# TRV_UP20.net
KiCad netlist of a schematic drawn in EAGLE
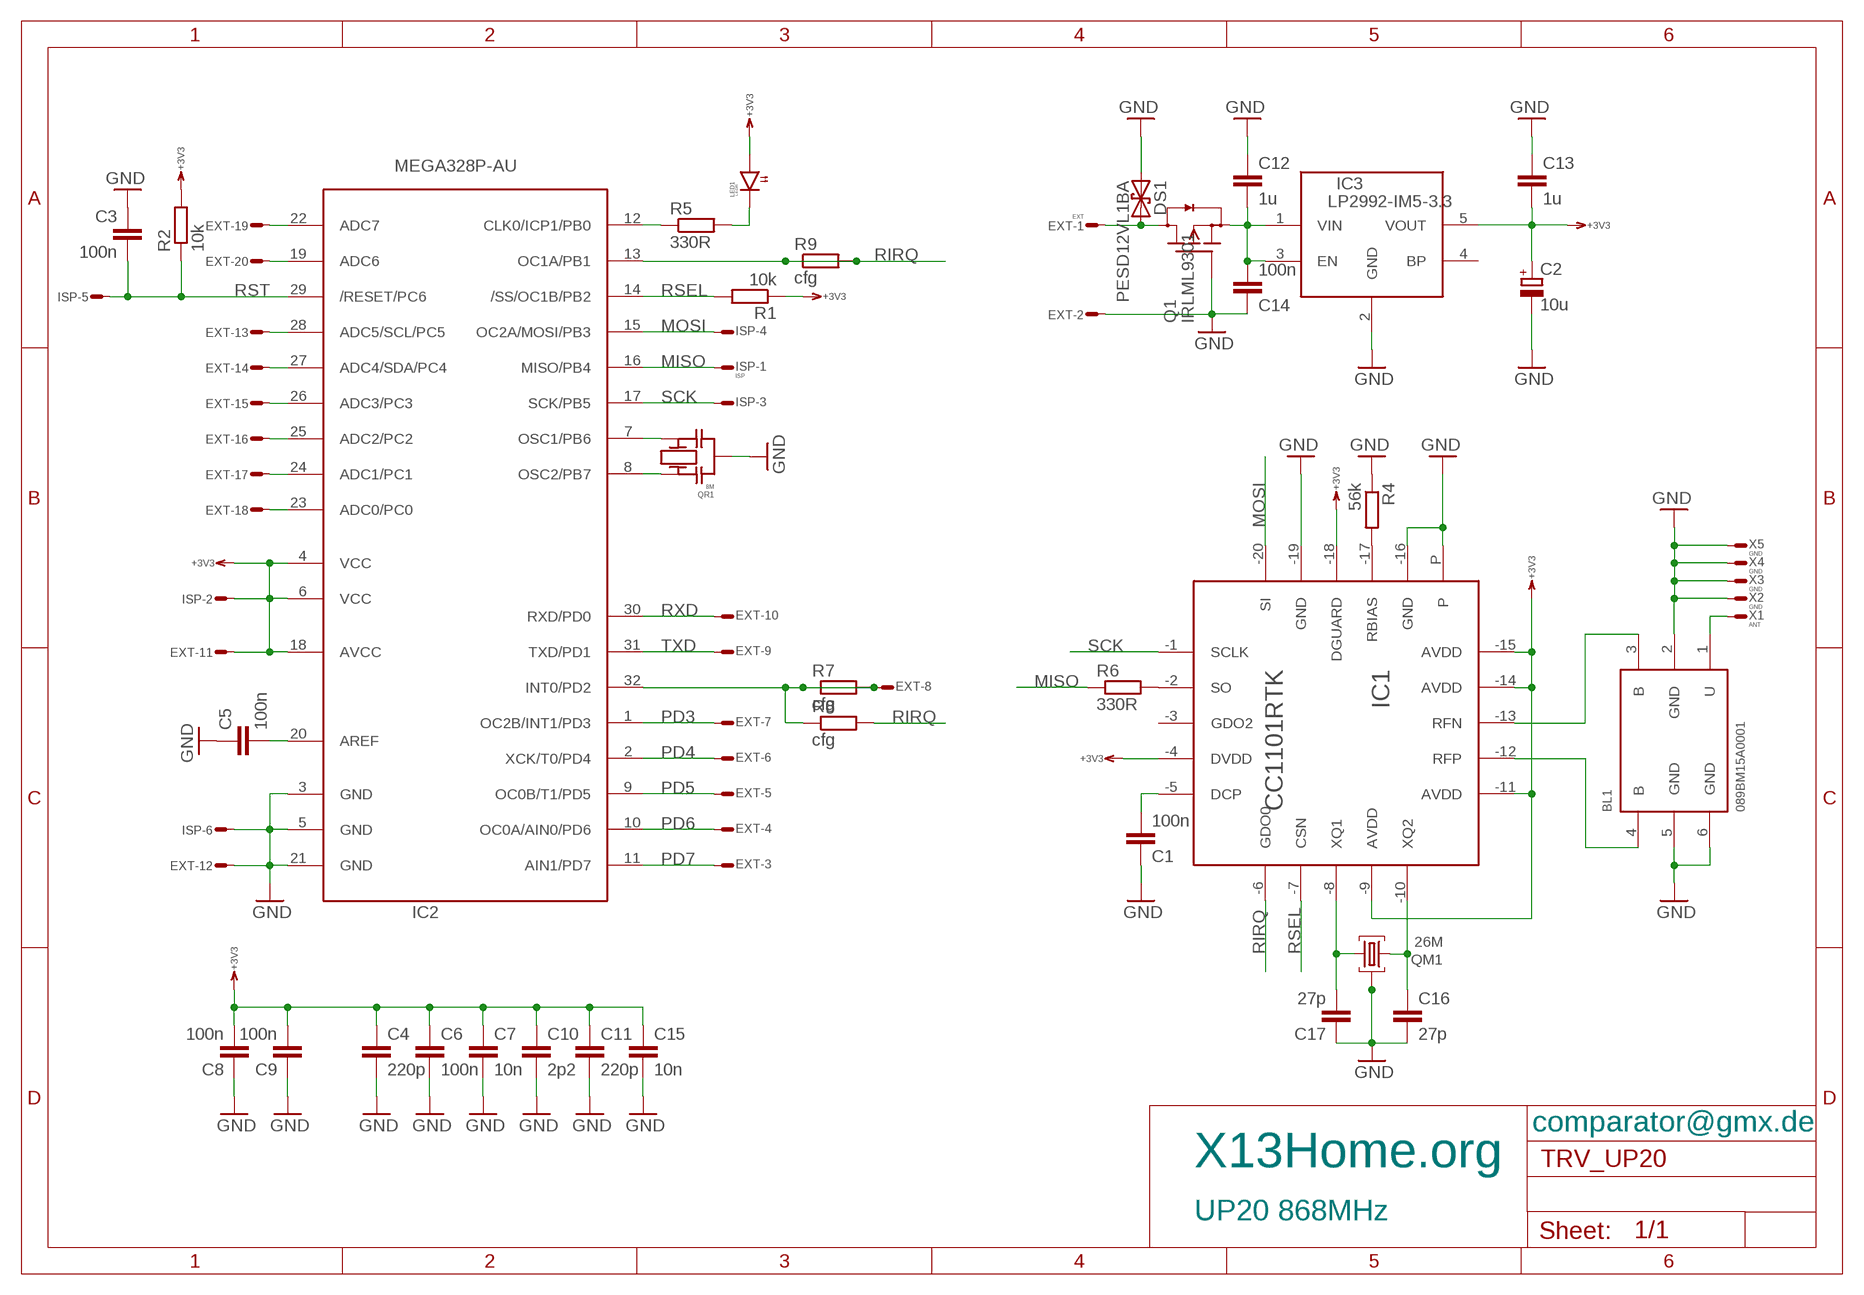
[diagram p0: schematic, sheet 1]

(export (version "E")
  (design (tool "Eeschema 10.0.6"))
  (components
    (comp (ref "BL1")
      (value "089BM15A0001")
      (footprint "eagle-import:BL")
      (libsource (lib "eagle-import") (part "BL"))
    )
    (comp (ref "C1")
      (value "100n")
      (footprint "eagle-import:0402")
      (libsource (lib "eagle-import") (part "C0402"))
    )
    (comp (ref "C2")
      (value "10u")
      (footprint "eagle-import:SMC_B")
      (libsource (lib "eagle-import") (part "C_POLSMCB"))
    )
    (comp (ref "C3")
      (value "100n")
      (footprint "eagle-import:0603")
      (libsource (lib "eagle-import") (part "C0603"))
    )
    (comp (ref "C4")
      (value "220p")
      (footprint "eagle-import:0402")
      (libsource (lib "eagle-import") (part "C0402"))
    )
    (comp (ref "C5")
      (value "100n")
      (footprint "eagle-import:0603")
      (libsource (lib "eagle-import") (part "C0603"))
    )
    (comp (ref "C6")
      (value "100n")
      (footprint "eagle-import:0402")
      (libsource (lib "eagle-import") (part "C0402"))
    )
    (comp (ref "C7")
      (value "10n")
      (footprint "eagle-import:0402")
      (libsource (lib "eagle-import") (part "C0402"))
    )
    (comp (ref "C8")
      (value "100n")
      (footprint "eagle-import:0603")
      (libsource (lib "eagle-import") (part "C0603"))
    )
    (comp (ref "C9")
      (value "100n")
      (footprint "eagle-import:0603")
      (libsource (lib "eagle-import") (part "C0603"))
    )
    (comp (ref "C10")
      (value "2p2")
      (footprint "eagle-import:0402")
      (libsource (lib "eagle-import") (part "C0402"))
    )
    (comp (ref "C11")
      (value "220p")
      (footprint "eagle-import:0402")
      (libsource (lib "eagle-import") (part "C0402"))
    )
    (comp (ref "C12")
      (value "1u")
      (footprint "eagle-import:0603")
      (libsource (lib "eagle-import") (part "C0603"))
    )
    (comp (ref "C13")
      (value "1u")
      (footprint "eagle-import:0603")
      (libsource (lib "eagle-import") (part "C0603"))
    )
    (comp (ref "C14")
      (value "100n")
      (footprint "eagle-import:0603")
      (libsource (lib "eagle-import") (part "C0603"))
    )
    (comp (ref "C15")
      (value "10n")
      (footprint "eagle-import:0402")
      (libsource (lib "eagle-import") (part "C0402"))
    )
    (comp (ref "C16")
      (value "27p")
      (footprint "eagle-import:0402")
      (libsource (lib "eagle-import") (part "C0402"))
    )
    (comp (ref "C17")
      (value "27p")
      (footprint "eagle-import:0402")
      (libsource (lib "eagle-import") (part "C0402"))
    )
    (comp (ref "DS1")
      (value "PESD12VL1BA")
      (footprint "eagle-import:SOD323")
      (libsource (lib "eagle-import") (part "TVS-U323"))
    )
    (comp (ref "EXT")
      (value "EXT")
      (footprint "eagle-import:ML20S")
      (libsource (lib "eagle-import") (part "ML20?ES"))
    )
    (comp (ref "IC1")
      (value "CC1101RTK")
      (footprint "eagle-import:VQFN20")
      (libsource (lib "eagle-import") (part "CC110L"))
    )
    (comp (ref "IC2")
      (value "MEGA328P-AU")
      (footprint "eagle-import:TQFP32-08")
      (libsource (lib "eagle-import") (part "MEGA168PA"))
    )
    (comp (ref "IC3")
      (value "LP2992-IM5-3.3")
      (footprint "eagle-import:SOT23-5")
      (libsource (lib "eagle-import") (part "LDO"))
    )
    (comp (ref "ISP")
      (value "ISP")
      (footprint "eagle-import:ML6S")
      (libsource (lib "eagle-import") (part "ML6ES"))
    )
    (comp (ref "LED1")
      (value "LEDR")
      (footprint "eagle-import:T1-3_4")
      (libsource (lib "eagle-import") (part "LEDT134"))
    )
    (comp (ref "Q1")
      (value "IRLML9301")
      (footprint "eagle-import:SOT23")
      (libsource (lib "eagle-import") (part "FET-PDSOT23"))
    )
    (comp (ref "QM1")
      (value "26M")
      (footprint "eagle-import:SMD_4P_3.2X2.5")
      (libsource (lib "eagle-import") (part "QM3.2X2.5"))
    )
    (comp (ref "QR1")
      (value "8M")
      (footprint "eagle-import:CSTCE")
      (libsource (lib "eagle-import") (part "QRCE"))
    )
    (comp (ref "R1")
      (value "10k")
      (footprint "eagle-import:0402")
      (libsource (lib "eagle-import") (part "R0402"))
    )
    (comp (ref "R2")
      (value "10k")
      (footprint "eagle-import:0603")
      (libsource (lib "eagle-import") (part "R0603"))
    )
    (comp (ref "R4")
      (value "56k")
      (footprint "eagle-import:0402")
      (libsource (lib "eagle-import") (part "R0402"))
    )
    (comp (ref "R5")
      (value "330R")
      (footprint "eagle-import:0402")
      (libsource (lib "eagle-import") (part "R0402"))
    )
    (comp (ref "R6")
      (value "330R")
      (footprint "eagle-import:0402")
      (libsource (lib "eagle-import") (part "R0402"))
    )
    (comp (ref "R7")
      (value "cfg")
      (footprint "eagle-import:0402")
      (libsource (lib "eagle-import") (part "R0402"))
    )
    (comp (ref "R8")
      (value "cfg")
      (footprint "eagle-import:0402")
      (libsource (lib "eagle-import") (part "R0402"))
    )
    (comp (ref "R9")
      (value "cfg")
      (footprint "eagle-import:0402")
      (libsource (lib "eagle-import") (part "R0402"))
    )
    (comp (ref "X1")
      (value "ANT")
      (footprint "eagle-import:S2.54_1.27")
      (libsource (lib "eagle-import") (part "WIREPADS2.54/1.27"))
    )
    (comp (ref "X2")
      (value "GND")
      (footprint "eagle-import:S2.54_1.27")
      (libsource (lib "eagle-import") (part "WIREPADS2.54/1.27"))
    )
    (comp (ref "X3")
      (value "GND")
      (footprint "eagle-import:S2.54_1.27")
      (libsource (lib "eagle-import") (part "WIREPADS2.54/1.27"))
    )
    (comp (ref "X4")
      (value "GND")
      (footprint "eagle-import:S2.54_1.27")
      (libsource (lib "eagle-import") (part "WIREPADS2.54/1.27"))
    )
    (comp (ref "X5")
      (value "GND")
      (footprint "eagle-import:S2.54_1.27")
      (libsource (lib "eagle-import") (part "WIREPADS2.54/1.27"))
    )
  )
  (nets
    (net (code "1") (name "+3V3") (class "Default")
      (node (ref "C10") (pin "1") (pinfunction "1_1") (pintype "passive"))
      (node (ref "C11") (pin "1") (pinfunction "1_1") (pintype "passive"))
      (node (ref "C13") (pin "2") (pinfunction "2_2") (pintype "passive"))
      (node (ref "C15") (pin "1") (pinfunction "1_1") (pintype "passive"))
      (node (ref "C2") (pin "+") (pinfunction "+_+") (pintype "passive"))
      (node (ref "C4") (pin "1") (pinfunction "1_1") (pintype "passive"))
      (node (ref "C6") (pin "1") (pinfunction "1_1") (pintype "passive"))
      (node (ref "C7") (pin "1") (pinfunction "1_1") (pintype "passive"))
      (node (ref "C8") (pin "2") (pinfunction "2_2") (pintype "passive"))
      (node (ref "C9") (pin "2") (pinfunction "2_2") (pintype "passive"))
      (node (ref "EXT") (pin "11") (pinfunction "S_11") (pintype "passive"))
      (node (ref "IC1") (pin "-11") (pinfunction "AVDD_-11") (pintype "bidirectional"))
      (node (ref "IC1") (pin "-14") (pinfunction "AVDD_-14") (pintype "bidirectional"))
      (node (ref "IC1") (pin "-15") (pinfunction "AVDD_-15") (pintype "bidirectional"))
      (node (ref "IC1") (pin "-18") (pinfunction "DGUARD_-18") (pintype "bidirectional"))
      (node (ref "IC1") (pin "-4") (pinfunction "DVDD_-4") (pintype "bidirectional"))
      (node (ref "IC1") (pin "-9") (pinfunction "AVDD_-9") (pintype "bidirectional"))
      (node (ref "IC2") (pin "18") (pinfunction "AVCC_18") (pintype "bidirectional"))
      (node (ref "IC2") (pin "4") (pinfunction "VCC_4") (pintype "bidirectional"))
      (node (ref "IC2") (pin "6") (pinfunction "VCC_6") (pintype "bidirectional"))
      (node (ref "IC3") (pin "5") (pinfunction "VOUT_5") (pintype "bidirectional"))
      (node (ref "ISP") (pin "2") (pinfunction "S_2") (pintype "passive"))
      (node (ref "LED1") (pin "A") (pinfunction "A_A") (pintype "bidirectional"))
      (node (ref "R1") (pin "1") (pinfunction "1_1") (pintype "passive"))
      (node (ref "R2") (pin "2") (pinfunction "2_2") (pintype "passive"))
    )
    (net (code "2") (name "/MISO") (class "Default")
      (node (ref "IC2") (pin "16") (pinfunction "MISO/PB4_16") (pintype "bidirectional"))
      (node (ref "ISP") (pin "1") (pinfunction "S_1") (pintype "passive"))
      (node (ref "R6") (pin "1") (pinfunction "1_1") (pintype "passive"))
    )
    (net (code "3") (name "/MOSI") (class "Default")
      (node (ref "IC1") (pin "-20") (pinfunction "SI_-20") (pintype "input"))
      (node (ref "IC2") (pin "15") (pinfunction "OC2A/MOSI/PB3_15") (pintype "bidirectional"))
      (node (ref "ISP") (pin "4") (pinfunction "S_4") (pintype "passive"))
    )
    (net (code "4") (name "/PD3") (class "Default")
      (node (ref "EXT") (pin "7") (pinfunction "S_7") (pintype "passive"))
      (node (ref "IC2") (pin "1") (pinfunction "OC2B/INT1/PD3_1") (pintype "bidirectional"))
    )
    (net (code "5") (name "/PD4") (class "Default")
      (node (ref "EXT") (pin "6") (pinfunction "S_6") (pintype "passive"))
      (node (ref "IC2") (pin "2") (pinfunction "XCK/T0/PD4_2") (pintype "bidirectional"))
    )
    (net (code "6") (name "/PD5") (class "Default")
      (node (ref "EXT") (pin "5") (pinfunction "S_5") (pintype "passive"))
      (node (ref "IC2") (pin "9") (pinfunction "OC0B/T1/PD5_9") (pintype "bidirectional"))
    )
    (net (code "7") (name "/PD6") (class "Default")
      (node (ref "EXT") (pin "4") (pinfunction "S_4") (pintype "passive"))
      (node (ref "IC2") (pin "10") (pinfunction "OC0A/AIN0/PD6_10") (pintype "bidirectional"))
    )
    (net (code "8") (name "/PD7") (class "Default")
      (node (ref "EXT") (pin "3") (pinfunction "S_3") (pintype "passive"))
      (node (ref "IC2") (pin "11") (pinfunction "AIN1/PD7_11") (pintype "bidirectional"))
    )
    (net (code "9") (name "/RIRQ") (class "Default")
      (node (ref "IC1") (pin "-6") (pinfunction "GDO0_-6") (pintype "bidirectional"))
      (node (ref "IC2") (pin "13") (pinfunction "OC1A/PB1_13") (pintype "bidirectional"))
      (node (ref "R8") (pin "2") (pinfunction "2_2") (pintype "passive"))
      (node (ref "R9") (pin "1") (pinfunction "1_1") (pintype "passive"))
      (node (ref "R9") (pin "2") (pinfunction "2_2") (pintype "passive"))
    )
    (net (code "10") (name "/RSEL") (class "Default")
      (node (ref "IC1") (pin "-7") (pinfunction "CSN_-7") (pintype "input"))
      (node (ref "IC2") (pin "14") (pinfunction "/SS/OC1B/PB2_14") (pintype "bidirectional"))
      (node (ref "R1") (pin "2") (pinfunction "2_2") (pintype "passive"))
    )
    (net (code "11") (name "/RST") (class "Default")
      (node (ref "C3") (pin "2") (pinfunction "2_2") (pintype "passive"))
      (node (ref "IC2") (pin "29") (pinfunction "/RESET/PC6_29") (pintype "bidirectional"))
      (node (ref "ISP") (pin "5") (pinfunction "S_5") (pintype "passive"))
      (node (ref "R2") (pin "1") (pinfunction "1_1") (pintype "passive"))
    )
    (net (code "12") (name "/RXD") (class "Default")
      (node (ref "EXT") (pin "10") (pinfunction "S_10") (pintype "passive"))
      (node (ref "IC2") (pin "30") (pinfunction "RXD/PD0_30") (pintype "bidirectional"))
    )
    (net (code "13") (name "/SCK") (class "Default")
      (node (ref "IC1") (pin "-1") (pinfunction "SCLK_-1") (pintype "input"))
      (node (ref "IC2") (pin "17") (pinfunction "SCK/PB5_17") (pintype "bidirectional"))
      (node (ref "ISP") (pin "3") (pinfunction "S_3") (pintype "passive"))
    )
    (net (code "14") (name "/TXD") (class "Default")
      (node (ref "EXT") (pin "9") (pinfunction "S_9") (pintype "passive"))
      (node (ref "IC2") (pin "31") (pinfunction "TXD/PD1_31") (pintype "bidirectional"))
    )
    (net (code "15") (name "GND") (class "Default")
      (node (ref "BL1") (pin "2") (pinfunction "GND_2") (pintype "bidirectional"))
      (node (ref "BL1") (pin "5") (pinfunction "GND_5") (pintype "bidirectional"))
      (node (ref "BL1") (pin "6") (pinfunction "GND_6") (pintype "bidirectional"))
      (node (ref "C1") (pin "1") (pinfunction "1_1") (pintype "passive"))
      (node (ref "C10") (pin "2") (pinfunction "2_2") (pintype "passive"))
      (node (ref "C11") (pin "2") (pinfunction "2_2") (pintype "passive"))
      (node (ref "C12") (pin "1") (pinfunction "1_1") (pintype "passive"))
      (node (ref "C13") (pin "1") (pinfunction "1_1") (pintype "passive"))
      (node (ref "C14") (pin "1") (pinfunction "1_1") (pintype "passive"))
      (node (ref "C15") (pin "2") (pinfunction "2_2") (pintype "passive"))
      (node (ref "C16") (pin "2") (pinfunction "2_2") (pintype "passive"))
      (node (ref "C17") (pin "1") (pinfunction "1_1") (pintype "passive"))
      (node (ref "C2") (pin "-") (pinfunction "-_-") (pintype "passive"))
      (node (ref "C3") (pin "1") (pinfunction "1_1") (pintype "passive"))
      (node (ref "C4") (pin "2") (pinfunction "2_2") (pintype "passive"))
      (node (ref "C5") (pin "1") (pinfunction "1_1") (pintype "passive"))
      (node (ref "C6") (pin "2") (pinfunction "2_2") (pintype "passive"))
      (node (ref "C7") (pin "2") (pinfunction "2_2") (pintype "passive"))
      (node (ref "C8") (pin "1") (pinfunction "1_1") (pintype "passive"))
      (node (ref "C9") (pin "1") (pinfunction "1_1") (pintype "passive"))
      (node (ref "DS1") (pin "A") (pinfunction "1_A") (pintype "passive"))
      (node (ref "EXT") (pin "12") (pinfunction "S_12") (pintype "passive"))
      (node (ref "EXT") (pin "2") (pinfunction "S_2") (pintype "passive"))
      (node (ref "IC1") (pin "-16") (pinfunction "GND_-16") (pintype "bidirectional"))
      (node (ref "IC1") (pin "-19") (pinfunction "GND_-19") (pintype "bidirectional"))
      (node (ref "IC1") (pin "P") (pinfunction "P_P") (pintype "bidirectional"))
      (node (ref "IC2") (pin "21") (pinfunction "GND_21") (pintype "bidirectional"))
      (node (ref "IC2") (pin "3") (pinfunction "GND_3") (pintype "bidirectional"))
      (node (ref "IC2") (pin "5") (pinfunction "GND_5") (pintype "bidirectional"))
      (node (ref "IC3") (pin "2") (pinfunction "GND_2") (pintype "bidirectional"))
      (node (ref "ISP") (pin "6") (pinfunction "S_6") (pintype "passive"))
      (node (ref "Q1") (pin "1") (pinfunction "G_1") (pintype "passive"))
      (node (ref "QM1") (pin "2") (pinfunction "M1_2") (pintype "passive"))
      (node (ref "QM1") (pin "4") (pinfunction "M2_4") (pintype "passive"))
      (node (ref "QR1") (pin "G") (pinfunction "M_G") (pintype "passive"))
      (node (ref "R4") (pin "1") (pinfunction "1_1") (pintype "passive"))
      (node (ref "X2") (pin "1") (pinfunction "S_1") (pintype "passive"))
      (node (ref "X3") (pin "1") (pinfunction "S_1") (pintype "passive"))
      (node (ref "X4") (pin "1") (pinfunction "S_1") (pintype "passive"))
      (node (ref "X5") (pin "1") (pinfunction "S_1") (pintype "passive"))
    )
    (net (code "16") (name "Net-(BL1-U)") (class "Default")
      (node (ref "BL1") (pin "1") (pinfunction "U_1") (pintype "bidirectional"))
      (node (ref "X1") (pin "1") (pinfunction "S_1") (pintype "passive"))
    )
    (net (code "17") (name "Net-(DS1-2)") (class "Default")
      (node (ref "DS1") (pin "C") (pinfunction "2_C") (pintype "passive"))
      (node (ref "EXT") (pin "1") (pinfunction "S_1") (pintype "passive"))
      (node (ref "Q1") (pin "3") (pinfunction "D_3") (pintype "passive"))
    )
    (net (code "18") (name "Net-(EXTE-S)") (class "Default")
      (node (ref "EXT") (pin "13") (pinfunction "S_13") (pintype "passive"))
      (node (ref "IC2") (pin "28") (pinfunction "ADC5/SCL/PC5_28") (pintype "bidirectional"))
    )
    (net (code "19") (name "Net-(EXTF-S)") (class "Default")
      (node (ref "EXT") (pin "14") (pinfunction "S_14") (pintype "passive"))
      (node (ref "IC2") (pin "27") (pinfunction "ADC4/SDA/PC4_27") (pintype "bidirectional"))
    )
    (net (code "20") (name "Net-(EXTG-S)") (class "Default")
      (node (ref "EXT") (pin "15") (pinfunction "S_15") (pintype "passive"))
      (node (ref "IC2") (pin "26") (pinfunction "ADC3/PC3_26") (pintype "bidirectional"))
    )
    (net (code "21") (name "Net-(EXTH-S)") (class "Default")
      (node (ref "EXT") (pin "16") (pinfunction "S_16") (pintype "passive"))
      (node (ref "IC2") (pin "25") (pinfunction "ADC2/PC2_25") (pintype "bidirectional"))
    )
    (net (code "22") (name "Net-(EXTI-S)") (class "Default")
      (node (ref "EXT") (pin "17") (pinfunction "S_17") (pintype "passive"))
      (node (ref "IC2") (pin "24") (pinfunction "ADC1/PC1_24") (pintype "bidirectional"))
    )
    (net (code "23") (name "Net-(EXTJ-S)") (class "Default")
      (node (ref "EXT") (pin "18") (pinfunction "S_18") (pintype "passive"))
      (node (ref "IC2") (pin "23") (pinfunction "ADC0/PC0_23") (pintype "bidirectional"))
    )
    (net (code "24") (name "Net-(EXTK-S)") (class "Default")
      (node (ref "EXT") (pin "19") (pinfunction "S_19") (pintype "passive"))
      (node (ref "IC2") (pin "22") (pinfunction "ADC7_22") (pintype "bidirectional"))
    )
    (net (code "25") (name "Net-(EXTM-S)") (class "Default")
      (node (ref "EXT") (pin "20") (pinfunction "S_20") (pintype "passive"))
      (node (ref "IC2") (pin "19") (pinfunction "ADC6_19") (pintype "bidirectional"))
    )
    (net (code "26") (name "Net-(EXTS-S)") (class "Default")
      (node (ref "EXT") (pin "8") (pinfunction "S_8") (pintype "passive"))
      (node (ref "IC2") (pin "32") (pinfunction "INT0/PD2_32") (pintype "bidirectional"))
      (node (ref "R7") (pin "1") (pinfunction "1_1") (pintype "passive"))
      (node (ref "R7") (pin "2") (pinfunction "2_2") (pintype "passive"))
      (node (ref "R8") (pin "1") (pinfunction "1_1") (pintype "passive"))
    )
    (net (code "27") (name "Net-(IC1-DCP)") (class "Default")
      (node (ref "C1") (pin "2") (pinfunction "2_2") (pintype "passive"))
      (node (ref "IC1") (pin "-5") (pinfunction "DCP_-5") (pintype "bidirectional"))
    )
    (net (code "28") (name "Net-(IC1-RBIAS)") (class "Default")
      (node (ref "IC1") (pin "-17") (pinfunction "RBIAS_-17") (pintype "bidirectional"))
      (node (ref "R4") (pin "2") (pinfunction "2_2") (pintype "passive"))
    )
    (net (code "29") (name "Net-(IC1-RFN)") (class "Default")
      (node (ref "BL1") (pin "3") (pinfunction "B_3") (pintype "bidirectional"))
      (node (ref "IC1") (pin "-13") (pinfunction "RFN_-13") (pintype "bidirectional"))
    )
    (net (code "30") (name "Net-(IC1-RFP)") (class "Default")
      (node (ref "BL1") (pin "4") (pinfunction "B_4") (pintype "bidirectional"))
      (node (ref "IC1") (pin "-12") (pinfunction "RFP_-12") (pintype "bidirectional"))
    )
    (net (code "31") (name "Net-(IC1-SO)") (class "Default")
      (node (ref "IC1") (pin "-2") (pinfunction "SO_-2") (pintype "output"))
      (node (ref "R6") (pin "2") (pinfunction "2_2") (pintype "passive"))
    )
    (net (code "32") (name "Net-(IC1-XQ1)") (class "Default")
      (node (ref "C17") (pin "2") (pinfunction "2_2") (pintype "passive"))
      (node (ref "IC1") (pin "-8") (pinfunction "XQ1_-8") (pintype "bidirectional"))
      (node (ref "QM1") (pin "3") (pinfunction "2_3") (pintype "passive"))
    )
    (net (code "33") (name "Net-(IC1-XQ2)") (class "Default")
      (node (ref "C16") (pin "1") (pinfunction "1_1") (pintype "passive"))
      (node (ref "IC1") (pin "-10") (pinfunction "XQ2_-10") (pintype "bidirectional"))
      (node (ref "QM1") (pin "1") (pinfunction "1_1") (pintype "passive"))
    )
    (net (code "34") (name "Net-(IC2-AREF)") (class "Default")
      (node (ref "C5") (pin "2") (pinfunction "2_2") (pintype "passive"))
      (node (ref "IC2") (pin "20") (pinfunction "AREF_20") (pintype "bidirectional"))
    )
    (net (code "35") (name "Net-(IC2-CLK0{slash}ICP1{slash}PB0)") (class "Default")
      (node (ref "IC2") (pin "12") (pinfunction "CLK0/ICP1/PB0_12") (pintype "bidirectional"))
      (node (ref "R5") (pin "1") (pinfunction "1_1") (pintype "passive"))
    )
    (net (code "36") (name "Net-(IC2-OSC1{slash}PB6)") (class "Default")
      (node (ref "IC2") (pin "7") (pinfunction "OSC1/PB6_7") (pintype "bidirectional"))
      (node (ref "QR1") (pin "B") (pinfunction "2_B") (pintype "passive"))
    )
    (net (code "37") (name "Net-(IC2-OSC2{slash}PB7)") (class "Default")
      (node (ref "IC2") (pin "8") (pinfunction "OSC2/PB7_8") (pintype "bidirectional"))
      (node (ref "QR1") (pin "A") (pinfunction "1_A") (pintype "passive"))
    )
    (net (code "38") (name "Net-(IC3-EN)") (class "Default")
      (node (ref "C12") (pin "2") (pinfunction "2_2") (pintype "passive"))
      (node (ref "C14") (pin "2") (pinfunction "2_2") (pintype "passive"))
      (node (ref "IC3") (pin "1") (pinfunction "VIN_1") (pintype "bidirectional"))
      (node (ref "IC3") (pin "3") (pinfunction "EN_3") (pintype "bidirectional"))
      (node (ref "Q1") (pin "2") (pinfunction "S_2") (pintype "passive"))
    )
    (net (code "39") (name "Net-(LED1-PadC)") (class "Default")
      (node (ref "LED1") (pin "C") (pinfunction "C_C") (pintype "bidirectional"))
      (node (ref "R5") (pin "2") (pinfunction "2_2") (pintype "passive"))
    )
    (net (code "40") (name "unconnected-(IC1-GDO2-Pad-3)") (class "Default")
      (node (ref "IC1") (pin "-3") (pinfunction "GDO2_-3") (pintype "output"))
    )
    (net (code "41") (name "unconnected-(IC3-BP-Pad4)") (class "Default")
      (node (ref "IC3") (pin "4") (pinfunction "BP_4") (pintype "bidirectional"))
    )
  )
)
